# Pyro_Cut-Down.net
KiCad netlist of a schematic drawn in EAGLE
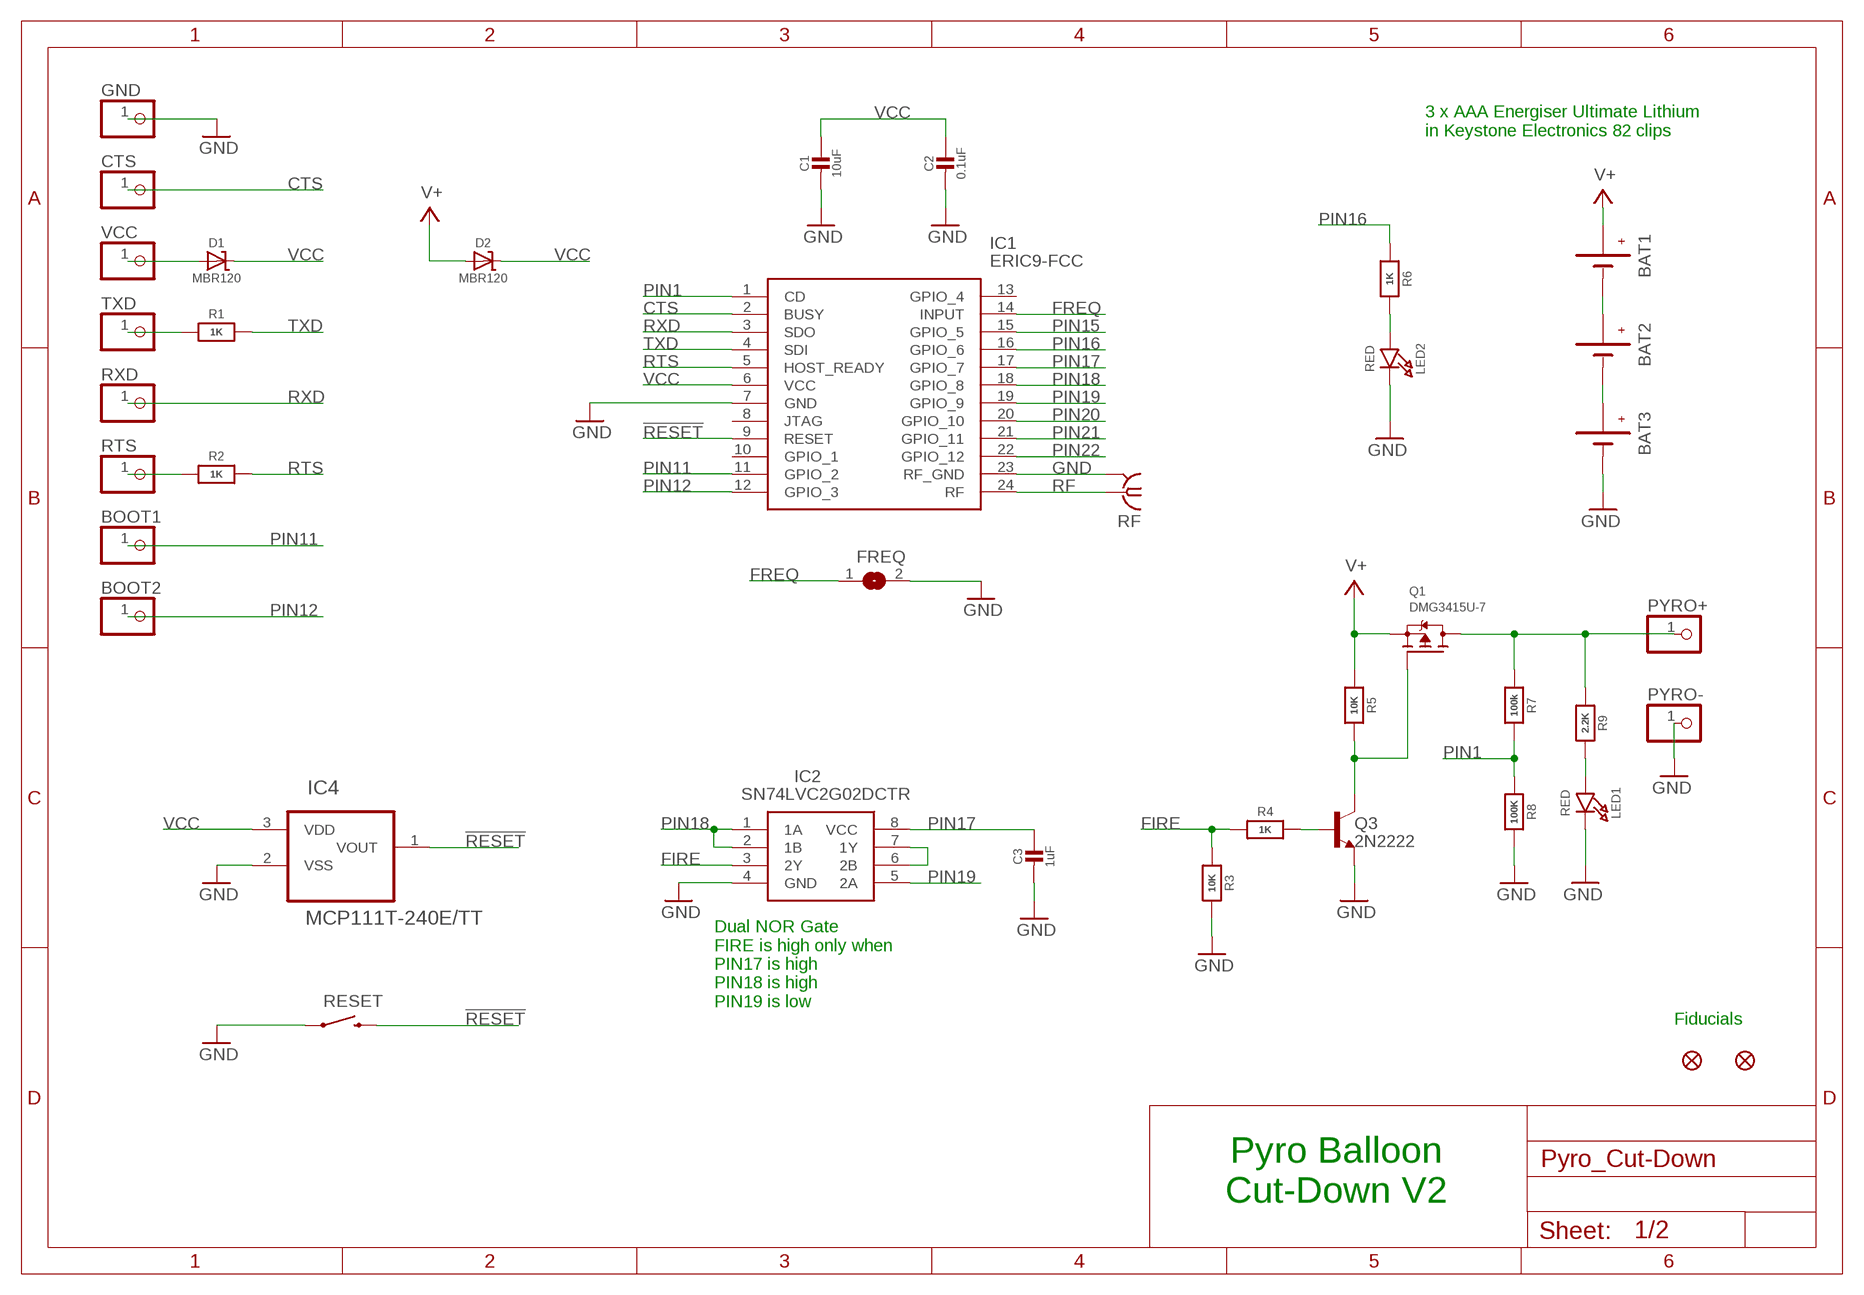
[diagram p0: schematic, sheet 1]
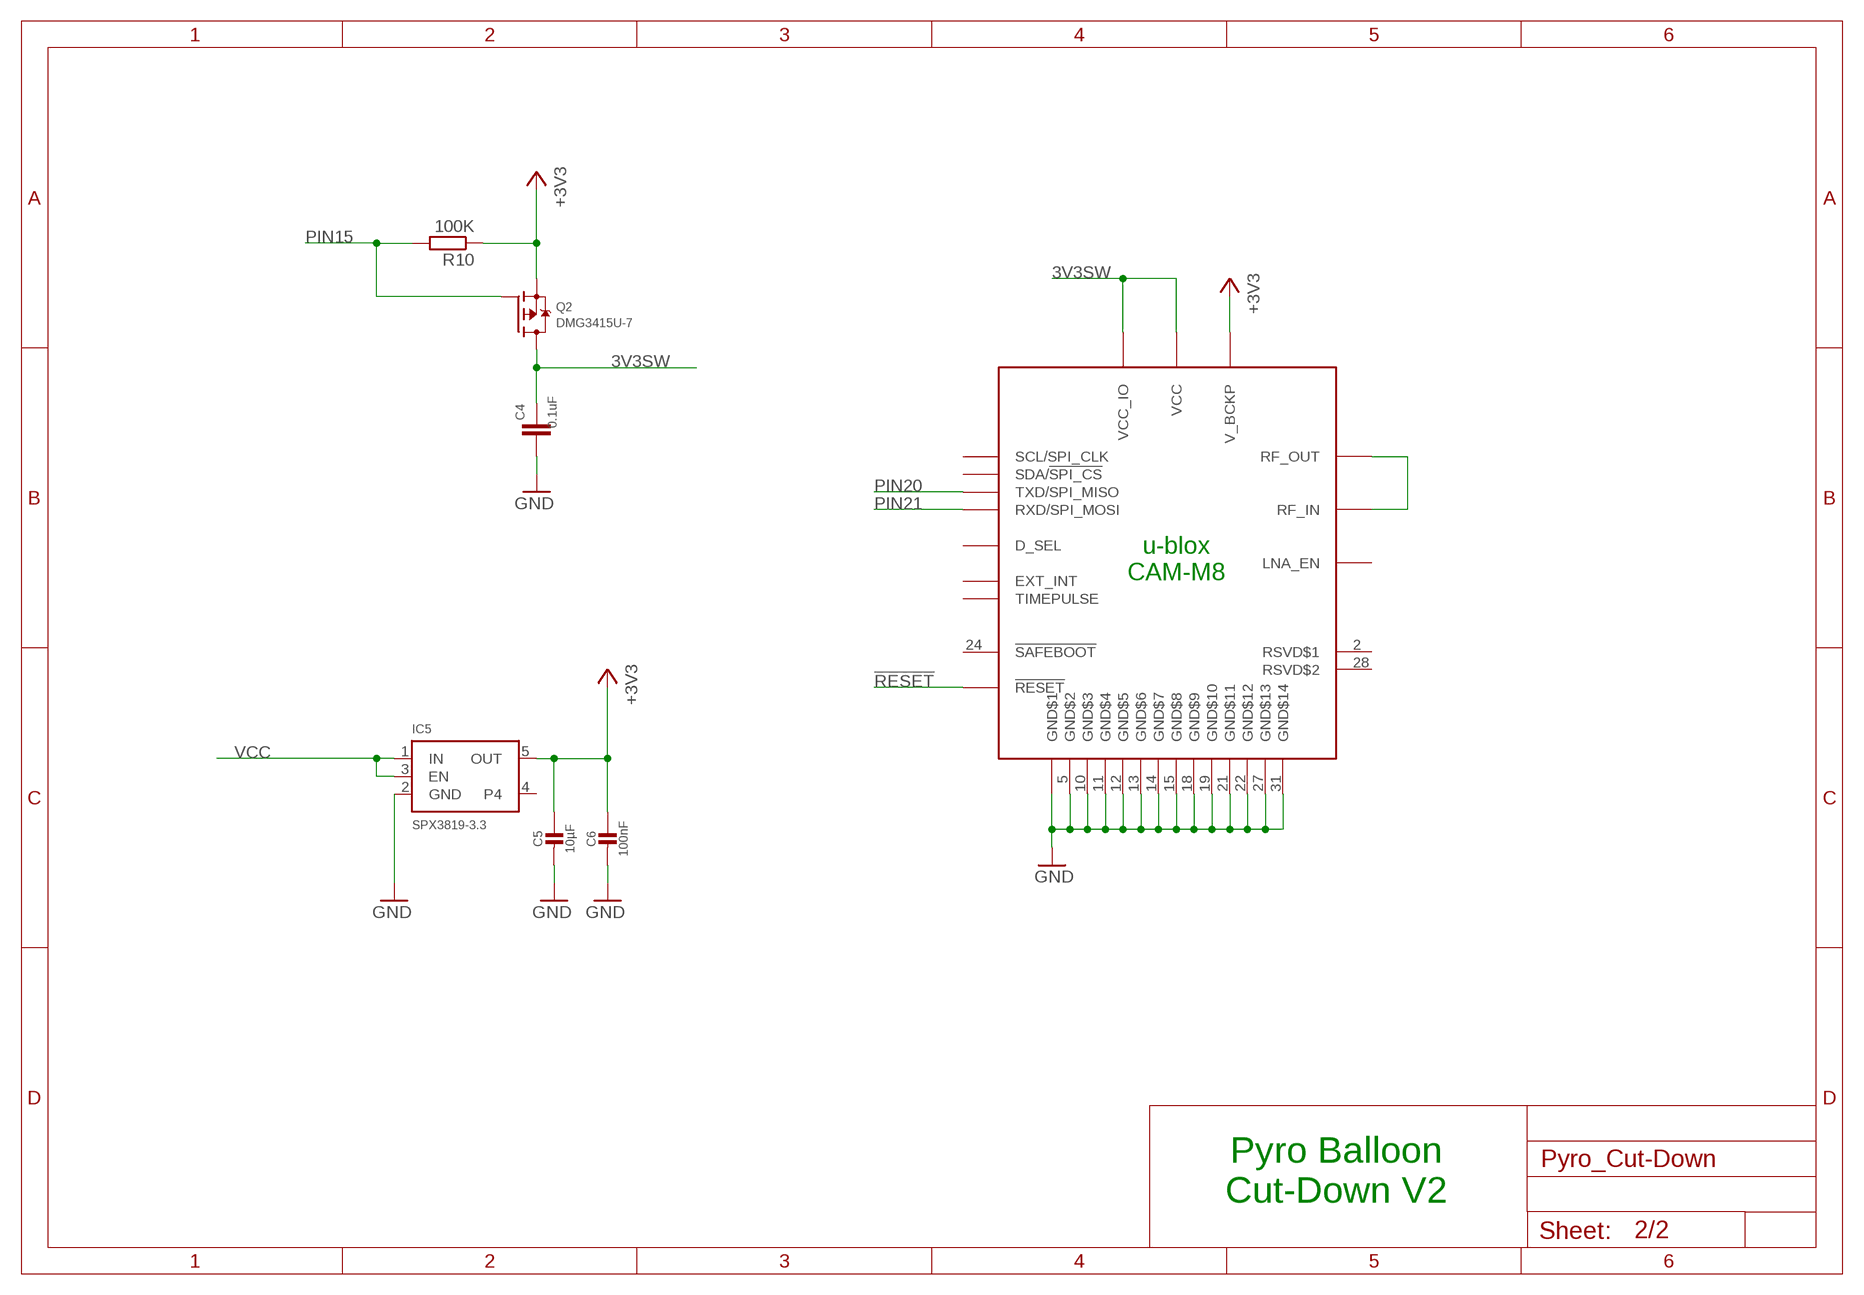
[diagram p1: schematic, sheet 2]

(export (version "E")
  (design (tool "Eeschema 10.0.6"))
  (components
    (comp (ref "C4")
      (value "0.1uF")
      (footprint "eagle-import:C0603")
      (libsource (lib "eagle-import") (part "C-EUC0603"))
    )
    (comp (ref "C5")
      (value "10µF")
      (footprint "eagle-import:0805-NO")
      (libsource (lib "eagle-import") (part "CAP_CERAMIC0805-NOOUTLINE"))
    )
    (comp (ref "C6")
      (value "100nF")
      (footprint "eagle-import:0603-NO")
      (libsource (lib "eagle-import") (part "CAP_CERAMIC0603_NO"))
    )
    (comp (ref "IC3")
      (value "CAM-M8")
      (footprint "eagle-import:CAM-M8")
      (libsource (lib "eagle-import") (part "CAM-M8"))
    )
    (comp (ref "IC5")
      (value "SPX3819-3.3")
      (footprint "eagle-import:SOT23-5")
      (libsource (lib "eagle-import") (part "VREG_SOT23-5"))
    )
    (comp (ref "Q2")
      (value "DMG3415U-7")
      (footprint "eagle-import:SOT23-WIDE")
      (libsource (lib "eagle-import") (part "MOSFET-PWIDE"))
    )
    (comp (ref "R10")
      (value "100K")
      (footprint "eagle-import:R0603")
      (libsource (lib "eagle-import") (part "R-EU_R0603"))
    )
    (comp (ref "BAT1")
      (value "BATTERYKEYSTONE82")
      (footprint "eagle-import:BATTERY-AAA-KEYSTONE82")
      (libsource (lib "eagle-import") (part "BATTERYKEYSTONE82"))
    )
    (comp (ref "BAT2")
      (value "BATTERYKEYSTONE82")
      (footprint "eagle-import:BATTERY-AAA-KEYSTONE82")
      (libsource (lib "eagle-import") (part "BATTERYKEYSTONE82"))
    )
    (comp (ref "BAT3")
      (value "BATTERYKEYSTONE82")
      (footprint "eagle-import:BATTERY-AAA-KEYSTONE82")
      (libsource (lib "eagle-import") (part "BATTERYKEYSTONE82"))
    )
    (comp (ref "BOOT1")
      (value "PINHD-1X1")
      (footprint "eagle-import:1X01")
      (libsource (lib "eagle-import") (part "PINHD-1X1"))
    )
    (comp (ref "BOOT2")
      (value "PINHD-1X1")
      (footprint "eagle-import:1X01")
      (libsource (lib "eagle-import") (part "PINHD-1X1"))
    )
    (comp (ref "C1")
      (value "10uF")
      (footprint "eagle-import:0805-NO")
      (libsource (lib "eagle-import") (part "CAP_CERAMIC0805-NOOUTLINE"))
    )
    (comp (ref "C2")
      (value "0.1uF")
      (footprint "eagle-import:0603-NO")
      (libsource (lib "eagle-import") (part "CAP_CERAMIC0603_NO"))
    )
    (comp (ref "C3")
      (value "1uF")
      (footprint "eagle-import:0603-NO")
      (libsource (lib "eagle-import") (part "CAP_CERAMIC0603_NO"))
    )
    (comp (ref "CTS")
      (value "PINHD-1X1")
      (footprint "eagle-import:1X01")
      (libsource (lib "eagle-import") (part "PINHD-1X1"))
    )
    (comp (ref "D1")
      (value "MBR120")
      (footprint "eagle-import:SOD-123")
      (libsource (lib "eagle-import") (part "DIODE-SCHOTTKYSOD-123"))
    )
    (comp (ref "D2")
      (value "MBR120")
      (footprint "eagle-import:SOD-123")
      (libsource (lib "eagle-import") (part "DIODE-SCHOTTKYSOD-123"))
    )
    (comp (ref "FD1")
      (value "FIDUCIAL1X2")
      (footprint "eagle-import:FIDUCIAL-1X2")
      (libsource (lib "eagle-import") (part "FIDUCIAL1X2"))
    )
    (comp (ref "FD2")
      (value "FIDUCIAL1X2")
      (footprint "eagle-import:FIDUCIAL-1X2")
      (libsource (lib "eagle-import") (part "FIDUCIAL1X2"))
    )
    (comp (ref "FREQ")
      (value "SOLDERJUMPER")
      (footprint "eagle-import:SOLDERJUMPER_ARROW_NOPASTE")
      (libsource (lib "eagle-import") (part "SOLDERJUMPER"))
    )
    (comp (ref "GND")
      (value "PINHD-1X1")
      (footprint "eagle-import:1X01")
      (libsource (lib "eagle-import") (part "PINHD-1X1"))
    )
    (comp (ref "IC1")
      (value "ERIC9-FCC")
      (footprint "eagle-import:ERIC4")
      (fields (field (name "ARROW_PART_NUMBER") "eRIC9-FCC"))
      (libsource (lib "eagle-import") (part "ERIC9-FCC"))
    )
    (comp (ref "IC2")
      (value "SN74LVC2G02DCTR")
      (footprint "eagle-import:SOP65P400X130-8N")
      (libsource (lib "eagle-import") (part "SN74LVC2G02DCTR"))
    )
    (comp (ref "IC4")
      (value "MCP111T-240E/TT")
      (footprint "eagle-import:SOT95P237X112-3N")
      (fields (field (name "MPN") "MCP111T-270E/TT") (field (name "MPN_1") "MCP111T-240E/TT"))
      (libsource (lib "eagle-import") (part "MCP111T-270E/TT"))
    )
    (comp (ref "LED1")
      (value "RED")
      (footprint "eagle-import:CHIPLED_0805_NOOUTLINE")
      (libsource (lib "eagle-import") (part "LED0805_NOOUTLINE"))
    )
    (comp (ref "LED2")
      (value "RED")
      (footprint "eagle-import:CHIPLED_0805_NOOUTLINE")
      (libsource (lib "eagle-import") (part "LED0805_NOOUTLINE"))
    )
    (comp (ref "PYRO+")
      (value "PINHD-1X1")
      (footprint "eagle-import:1X01")
      (libsource (lib "eagle-import") (part "PINHD-1X1"))
    )
    (comp (ref "PYRO-")
      (value "PINHD-1X1")
      (footprint "eagle-import:1X01")
      (libsource (lib "eagle-import") (part "PINHD-1X1"))
    )
    (comp (ref "Q1")
      (value "DMG3415U-7")
      (footprint "eagle-import:SOT23-WIDE")
      (libsource (lib "eagle-import") (part "MOSFET-PWIDE"))
    )
    (comp (ref "Q3")
      (value "2N2222")
      (footprint "eagle-import:SOT23-BEC")
      (libsource (lib "eagle-import") (part "-NPN-SOT23-BECMMBT2222ALT1"))
    )
    (comp (ref "R1")
      (value "1K")
      (footprint "eagle-import:0603-NO")
      (libsource (lib "eagle-import") (part "RESISTOR_0603_NOOUT"))
    )
    (comp (ref "R2")
      (value "1K")
      (footprint "eagle-import:0603-NO")
      (libsource (lib "eagle-import") (part "RESISTOR_0603_NOOUT"))
    )
    (comp (ref "R3")
      (value "10K")
      (footprint "eagle-import:0603-NO")
      (libsource (lib "eagle-import") (part "RESISTOR_0603_NOOUT"))
    )
    (comp (ref "R4")
      (value "1K")
      (footprint "eagle-import:0603-NO")
      (libsource (lib "eagle-import") (part "RESISTOR_0603_NOOUT"))
    )
    (comp (ref "R5")
      (value "10K")
      (footprint "eagle-import:0603-NO")
      (libsource (lib "eagle-import") (part "RESISTOR_0603_NOOUT"))
    )
    (comp (ref "R6")
      (value "1K")
      (footprint "eagle-import:0603-NO")
      (libsource (lib "eagle-import") (part "RESISTOR_0603_NOOUT"))
    )
    (comp (ref "R7")
      (value "100k")
      (footprint "eagle-import:0603-NO")
      (libsource (lib "eagle-import") (part "RESISTOR_0603_NOOUT"))
    )
    (comp (ref "R8")
      (value "100K")
      (footprint "eagle-import:0603-NO")
      (libsource (lib "eagle-import") (part "RESISTOR_0603_NOOUT"))
    )
    (comp (ref "R9")
      (value "2.2K")
      (footprint "eagle-import:0603-NO")
      (libsource (lib "eagle-import") (part "RESISTOR_0603_NOOUT"))
    )
    (comp (ref "RESET")
      (value "SWITCH-MOMENTARY-2PTH")
      (footprint "eagle-import:TACTILE-PTH")
      (libsource (lib "eagle-import") (part "SWITCH-MOMENTARY-2PTH"))
    )
    (comp (ref "RF")
      (value "SMA-142-0711-821/826")
      (footprint "eagle-import:J502-ND-142-0711-821_826")
      (fields (field (name "MF") "JOHNSON COMPONENTS") (field (name "MPN") "142-0711-821"))
      (libsource (lib "eagle-import") (part "SMA-142-0711-821/826"))
    )
    (comp (ref "RTS")
      (value "PINHD-1X1")
      (footprint "eagle-import:1X01")
      (libsource (lib "eagle-import") (part "PINHD-1X1"))
    )
    (comp (ref "RXD")
      (value "PINHD-1X1")
      (footprint "eagle-import:1X01")
      (libsource (lib "eagle-import") (part "PINHD-1X1"))
    )
    (comp (ref "TXD")
      (value "PINHD-1X1")
      (footprint "eagle-import:1X01")
      (libsource (lib "eagle-import") (part "PINHD-1X1"))
    )
    (comp (ref "VCC")
      (value "PINHD-1X1")
      (footprint "eagle-import:1X01")
      (libsource (lib "eagle-import") (part "PINHD-1X1"))
    )
  )
  (nets
    (net (code "1") (name "+3V3") (class "Default")
      (node (ref "C5") (pin "1") (pinfunction "1_1") (pintype "passive"))
      (node (ref "C6") (pin "1") (pinfunction "1_1") (pintype "passive"))
      (node (ref "IC3") (pin "8") (pinfunction "V_BCKP_8") (pintype "power_in"))
      (node (ref "IC5") (pin "5") (pinfunction "OUT_5") (pintype "power_in"))
      (node (ref "Q2") (pin "2") (pinfunction "S_2") (pintype "passive"))
      (node (ref "R10") (pin "1") (pinfunction "1_1") (pintype "passive"))
    )
    (net (code "2") (name "3V3SW") (class "Default")
      (node (ref "C4") (pin "1") (pinfunction "1_1") (pintype "passive"))
      (node (ref "IC3") (pin "1") (pinfunction "VCC_IO_1") (pintype "power_in"))
      (node (ref "IC3") (pin "9") (pinfunction "VCC_9") (pintype "power_in"))
      (node (ref "Q2") (pin "3") (pinfunction "D_3") (pintype "passive"))
    )
    (net (code "3") (name "CTS") (class "Default")
      (node (ref "CTS") (pin "1") (pinfunction "1_1") (pintype "passive"))
      (node (ref "IC1") (pin "2") (pinfunction "BUSY_2") (pintype "bidirectional"))
    )
    (net (code "4") (name "FIRE") (class "Default")
      (node (ref "IC2") (pin "3") (pinfunction "2Y_3") (pintype "bidirectional"))
      (node (ref "R3") (pin "1") (pinfunction "1_1") (pintype "passive"))
      (node (ref "R4") (pin "1") (pinfunction "1_1") (pintype "passive"))
    )
    (net (code "5") (name "FREQ") (class "Default")
      (node (ref "FREQ") (pin "1") (pinfunction "1_1") (pintype "passive"))
      (node (ref "IC1") (pin "14") (pinfunction "INPUT_14") (pintype "bidirectional"))
    )
    (net (code "6") (name "GND") (class "Default")
      (node (ref "BAT3") (pin "GND@1") (pinfunction "-_GND@1") (pintype "power_in"))
      (node (ref "BAT3") (pin "GND@2") (pinfunction "-_GND@2") (pintype "power_in"))
      (node (ref "C1") (pin "2") (pinfunction "2_2") (pintype "passive"))
      (node (ref "C2") (pin "2") (pinfunction "2_2") (pintype "passive"))
      (node (ref "C3") (pin "2") (pinfunction "2_2") (pintype "passive"))
      (node (ref "C4") (pin "2") (pinfunction "2_2") (pintype "passive"))
      (node (ref "C5") (pin "2") (pinfunction "2_2") (pintype "passive"))
      (node (ref "C6") (pin "2") (pinfunction "2_2") (pintype "passive"))
      (node (ref "FREQ") (pin "2") (pinfunction "2_2") (pintype "passive"))
      (node (ref "GND") (pin "1") (pinfunction "1_1") (pintype "passive"))
      (node (ref "IC1") (pin "23") (pinfunction "RF_GND_23") (pintype "bidirectional"))
      (node (ref "IC1") (pin "7") (pinfunction "GND_7") (pintype "bidirectional"))
      (node (ref "IC2") (pin "4") (pinfunction "GND_4") (pintype "bidirectional"))
      (node (ref "IC3") (pin "10") (pinfunction "GND$3_10") (pintype "power_in"))
      (node (ref "IC3") (pin "11") (pinfunction "GND$4_11") (pintype "power_in"))
      (node (ref "IC3") (pin "12") (pinfunction "GND$5_12") (pintype "power_in"))
      (node (ref "IC3") (pin "13") (pinfunction "GND$6_13") (pintype "power_in"))
      (node (ref "IC3") (pin "14") (pinfunction "GND$7_14") (pintype "power_in"))
      (node (ref "IC3") (pin "15") (pinfunction "GND$8_15") (pintype "power_in"))
      (node (ref "IC3") (pin "18") (pinfunction "GND$9_18") (pintype "power_in"))
      (node (ref "IC3") (pin "19") (pinfunction "GND$10_19") (pintype "power_in"))
      (node (ref "IC3") (pin "21") (pinfunction "GND$11_21") (pintype "power_in"))
      (node (ref "IC3") (pin "22") (pinfunction "GND$12_22") (pintype "power_in"))
      (node (ref "IC3") (pin "27") (pinfunction "GND$13_27") (pintype "power_in"))
      (node (ref "IC3") (pin "31") (pinfunction "GND$14_31") (pintype "power_in"))
      (node (ref "IC3") (pin "4") (pinfunction "GND$1_4") (pintype "power_in"))
      (node (ref "IC3") (pin "5") (pinfunction "GND$2_5") (pintype "power_in"))
      (node (ref "IC4") (pin "2") (pinfunction "VSS_2") (pintype "power_in"))
      (node (ref "IC5") (pin "2") (pinfunction "GND_2") (pintype "power_in"))
      (node (ref "LED1") (pin "C") (pinfunction "C_C") (pintype "passive"))
      (node (ref "LED2") (pin "C") (pinfunction "C_C") (pintype "passive"))
      (node (ref "PYRO-") (pin "1") (pinfunction "1_1") (pintype "passive"))
      (node (ref "Q3") (pin "E") (pinfunction "E_E") (pintype "passive"))
      (node (ref "R3") (pin "2") (pinfunction "2_2") (pintype "passive"))
      (node (ref "R8") (pin "2") (pinfunction "2_2") (pintype "passive"))
      (node (ref "RESET") (pin "1") (pinfunction "1_1") (pintype "passive"))
      (node (ref "RF") (pin "G@1") (pinfunction "2_G@1") (pintype "passive"))
      (node (ref "RF") (pin "G@2") (pinfunction "2_G@2") (pintype "passive"))
      (node (ref "RF") (pin "G@3") (pinfunction "2_G@3") (pintype "passive"))
      (node (ref "RF") (pin "G@4") (pinfunction "2_G@4") (pintype "passive"))
    )
    (net (code "7") (name "Net-(BAT1---PadGND@1)") (class "Default")
      (node (ref "BAT1") (pin "GND@1") (pinfunction "-_GND@1") (pintype "power_in"))
      (node (ref "BAT1") (pin "GND@2") (pinfunction "-_GND@2") (pintype "power_in"))
      (node (ref "BAT2") (pin "PWR@1") (pinfunction "+_PWR@1") (pintype "power_in"))
      (node (ref "BAT2") (pin "PWR@2") (pinfunction "+_PWR@2") (pintype "power_in"))
    )
    (net (code "8") (name "Net-(BAT2---PadGND@1)") (class "Default")
      (node (ref "BAT2") (pin "GND@1") (pinfunction "-_GND@1") (pintype "power_in"))
      (node (ref "BAT2") (pin "GND@2") (pinfunction "-_GND@2") (pintype "power_in"))
      (node (ref "BAT3") (pin "PWR@1") (pinfunction "+_PWR@1") (pintype "power_in"))
      (node (ref "BAT3") (pin "PWR@2") (pinfunction "+_PWR@2") (pintype "power_in"))
    )
    (net (code "9") (name "Net-(D1-PadA)") (class "Default")
      (node (ref "D1") (pin "A") (pinfunction "A_A") (pintype "passive"))
      (node (ref "VCC") (pin "1") (pinfunction "1_1") (pintype "passive"))
    )
    (net (code "10") (name "Net-(IC2-1Y)") (class "Default")
      (node (ref "IC2") (pin "6") (pinfunction "2B_6") (pintype "bidirectional"))
      (node (ref "IC2") (pin "7") (pinfunction "1Y_7") (pintype "bidirectional"))
    )
    (net (code "11") (name "Net-(IC3-RF_IN)") (class "Default")
      (node (ref "IC3") (pin "16") (pinfunction "RF_OUT_16") (pintype "output"))
      (node (ref "IC3") (pin "17") (pinfunction "RF_IN_17") (pintype "input"))
    )
    (net (code "12") (name "Net-(LED1-PadA)") (class "Default")
      (node (ref "LED1") (pin "A") (pinfunction "A_A") (pintype "passive"))
      (node (ref "R9") (pin "2") (pinfunction "2_2") (pintype "passive"))
    )
    (net (code "13") (name "Net-(LED2-PadA)") (class "Default")
      (node (ref "LED2") (pin "A") (pinfunction "A_A") (pintype "passive"))
      (node (ref "R6") (pin "2") (pinfunction "2_2") (pintype "passive"))
    )
    (net (code "14") (name "Net-(Q1-D)") (class "Default")
      (node (ref "PYRO+") (pin "1") (pinfunction "1_1") (pintype "passive"))
      (node (ref "Q1") (pin "3") (pinfunction "D_3") (pintype "passive"))
      (node (ref "R7") (pin "1") (pinfunction "1_1") (pintype "passive"))
      (node (ref "R9") (pin "1") (pinfunction "1_1") (pintype "passive"))
    )
    (net (code "15") (name "Net-(Q1-G)") (class "Default")
      (node (ref "Q1") (pin "1") (pinfunction "G_1") (pintype "passive"))
      (node (ref "Q3") (pin "C") (pinfunction "C_C") (pintype "passive"))
      (node (ref "R5") (pin "2") (pinfunction "2_2") (pintype "passive"))
    )
    (net (code "16") (name "Net-(Q3-PadB)") (class "Default")
      (node (ref "Q3") (pin "B") (pinfunction "B_B") (pintype "passive"))
      (node (ref "R4") (pin "2") (pinfunction "2_2") (pintype "passive"))
    )
    (net (code "17") (name "Net-(R1-Pad1)") (class "Default")
      (node (ref "R1") (pin "1") (pinfunction "1_1") (pintype "passive"))
      (node (ref "TXD") (pin "1") (pinfunction "1_1") (pintype "passive"))
    )
    (net (code "18") (name "Net-(R2-Pad1)") (class "Default")
      (node (ref "R2") (pin "1") (pinfunction "1_1") (pintype "passive"))
      (node (ref "RTS") (pin "1") (pinfunction "1_1") (pintype "passive"))
    )
    (net (code "19") (name "PIN1") (class "Default")
      (node (ref "IC1") (pin "1") (pinfunction "CD_1") (pintype "bidirectional"))
      (node (ref "R7") (pin "2") (pinfunction "2_2") (pintype "passive"))
      (node (ref "R8") (pin "1") (pinfunction "1_1") (pintype "passive"))
    )
    (net (code "20") (name "PIN11") (class "Default")
      (node (ref "BOOT1") (pin "1") (pinfunction "1_1") (pintype "passive"))
      (node (ref "IC1") (pin "11") (pinfunction "GPIO_2_11") (pintype "bidirectional"))
    )
    (net (code "21") (name "PIN12") (class "Default")
      (node (ref "BOOT2") (pin "1") (pinfunction "1_1") (pintype "passive"))
      (node (ref "IC1") (pin "12") (pinfunction "GPIO_3_12") (pintype "bidirectional"))
    )
    (net (code "22") (name "PIN15") (class "Default")
      (node (ref "IC1") (pin "15") (pinfunction "GPIO_5_15") (pintype "bidirectional"))
      (node (ref "Q2") (pin "1") (pinfunction "G_1") (pintype "passive"))
      (node (ref "R10") (pin "2") (pinfunction "2_2") (pintype "passive"))
    )
    (net (code "23") (name "PIN16") (class "Default")
      (node (ref "IC1") (pin "16") (pinfunction "GPIO_6_16") (pintype "bidirectional"))
      (node (ref "R6") (pin "1") (pinfunction "1_1") (pintype "passive"))
    )
    (net (code "24") (name "PIN17") (class "Default")
      (node (ref "C3") (pin "1") (pinfunction "1_1") (pintype "passive"))
      (node (ref "IC1") (pin "17") (pinfunction "GPIO_7_17") (pintype "bidirectional"))
      (node (ref "IC2") (pin "8") (pinfunction "VCC_8") (pintype "bidirectional"))
    )
    (net (code "25") (name "PIN18") (class "Default")
      (node (ref "IC1") (pin "18") (pinfunction "GPIO_8_18") (pintype "bidirectional"))
      (node (ref "IC2") (pin "1") (pinfunction "1A_1") (pintype "bidirectional"))
      (node (ref "IC2") (pin "2") (pinfunction "1B_2") (pintype "bidirectional"))
    )
    (net (code "26") (name "PIN19") (class "Default")
      (node (ref "IC1") (pin "19") (pinfunction "GPIO_9_19") (pintype "bidirectional"))
      (node (ref "IC2") (pin "5") (pinfunction "2A_5") (pintype "bidirectional"))
    )
    (net (code "27") (name "PIN20") (class "Default")
      (node (ref "IC1") (pin "20") (pinfunction "GPIO_10_20") (pintype "bidirectional"))
      (node (ref "IC3") (pin "25") (pinfunction "TXD/SPI_MISO_25") (pintype "output"))
    )
    (net (code "28") (name "PIN21") (class "Default")
      (node (ref "IC1") (pin "21") (pinfunction "GPIO_11_21") (pintype "bidirectional"))
      (node (ref "IC3") (pin "26") (pinfunction "RXD/SPI_MOSI_26") (pintype "input"))
    )
    (net (code "29") (name "PIN22") (class "Default")
      (node (ref "IC1") (pin "22") (pinfunction "GPIO_12_22") (pintype "bidirectional"))
    )
    (net (code "30") (name "RF") (class "Default")
      (node (ref "IC1") (pin "24") (pinfunction "RF_24") (pintype "bidirectional"))
      (node (ref "RF") (pin "1") (pinfunction "1_1") (pintype "passive"))
    )
    (net (code "31") (name "RTS") (class "Default")
      (node (ref "IC1") (pin "5") (pinfunction "HOST_READY_5") (pintype "bidirectional"))
      (node (ref "R2") (pin "2") (pinfunction "2_2") (pintype "passive"))
    )
    (net (code "32") (name "RXD") (class "Default")
      (node (ref "IC1") (pin "3") (pinfunction "SDO_3") (pintype "bidirectional"))
      (node (ref "RXD") (pin "1") (pinfunction "1_1") (pintype "passive"))
    )
    (net (code "33") (name "TXD") (class "Default")
      (node (ref "IC1") (pin "4") (pinfunction "SDI_4") (pintype "bidirectional"))
      (node (ref "R1") (pin "2") (pinfunction "2_2") (pintype "passive"))
    )
    (net (code "34") (name "V+") (class "Default")
      (node (ref "BAT1") (pin "PWR@1") (pinfunction "+_PWR@1") (pintype "power_in"))
      (node (ref "BAT1") (pin "PWR@2") (pinfunction "+_PWR@2") (pintype "power_in"))
      (node (ref "D2") (pin "A") (pinfunction "A_A") (pintype "passive"))
      (node (ref "Q1") (pin "2") (pinfunction "S_2") (pintype "passive"))
      (node (ref "R5") (pin "1") (pinfunction "1_1") (pintype "passive"))
    )
    (net (code "35") (name "VCC") (class "Default")
      (node (ref "C1") (pin "1") (pinfunction "1_1") (pintype "passive"))
      (node (ref "C2") (pin "1") (pinfunction "1_1") (pintype "passive"))
      (node (ref "D1") (pin "C") (pinfunction "C_C") (pintype "passive"))
      (node (ref "D2") (pin "C") (pinfunction "C_C") (pintype "passive"))
      (node (ref "IC1") (pin "6") (pinfunction "VCC_6") (pintype "bidirectional"))
      (node (ref "IC4") (pin "3") (pinfunction "VDD_3") (pintype "power_in"))
      (node (ref "IC5") (pin "1") (pinfunction "IN_1") (pintype "power_in"))
      (node (ref "IC5") (pin "3") (pinfunction "EN_3") (pintype "input"))
    )
    (net (code "36") (name "unconnected-(IC1-GPIO_1-Pad10)") (class "Default")
      (node (ref "IC1") (pin "10") (pinfunction "GPIO_1_10") (pintype "bidirectional"))
    )
    (net (code "37") (name "unconnected-(IC1-GPIO_4-Pad13)") (class "Default")
      (node (ref "IC1") (pin "13") (pinfunction "GPIO_4_13") (pintype "bidirectional"))
    )
    (net (code "38") (name "unconnected-(IC1-JTAG-Pad8)") (class "Default")
      (node (ref "IC1") (pin "8") (pinfunction "JTAG_8") (pintype "bidirectional"))
    )
    (net (code "39") (name "unconnected-(IC3-D_SEL-Pad20)") (class "Default")
      (node (ref "IC3") (pin "20") (pinfunction "D_SEL_20") (pintype "input"))
    )
    (net (code "40") (name "unconnected-(IC3-EXT_INT-Pad7)") (class "Default")
      (node (ref "IC3") (pin "7") (pinfunction "EXT_INT_7") (pintype "bidirectional"))
    )
    (net (code "41") (name "unconnected-(IC3-LNA_EN-Pad30)") (class "Default")
      (node (ref "IC3") (pin "30") (pinfunction "LNA_EN_30") (pintype "output"))
    )
    (net (code "42") (name "unconnected-(IC3-RSVD$1-Pad2)") (class "Default")
      (node (ref "IC3") (pin "2") (pinfunction "RSVD$1_2") (pintype "no_connect"))
    )
    (net (code "43") (name "unconnected-(IC3-RSVD$2-Pad28)") (class "Default")
      (node (ref "IC3") (pin "28") (pinfunction "RSVD$2_28") (pintype "no_connect"))
    )
    (net (code "44") (name "unconnected-(IC3-SCL{slash}SPI_CLK-Pad6)") (class "Default")
      (node (ref "IC3") (pin "6") (pinfunction "SCL/SPI_CLK_6") (pintype "input"))
    )
    (net (code "45") (name "unconnected-(IC3-SDA{slash}~{SPI_CS}-Pad3)") (class "Default")
      (node (ref "IC3") (pin "3") (pinfunction "SDA/~{SPI_CS}_3") (pintype "bidirectional"))
    )
    (net (code "46") (name "unconnected-(IC3-TIMEPULSE-Pad29)") (class "Default")
      (node (ref "IC3") (pin "29") (pinfunction "TIMEPULSE_29") (pintype "output"))
    )
    (net (code "47") (name "unconnected-(IC3-~{SAFEBOOT}-Pad24)") (class "Default")
      (node (ref "IC3") (pin "24") (pinfunction "~{SAFEBOOT}_24") (pintype "input"))
    )
    (net (code "48") (name "unconnected-(IC5-P4-Pad4)") (class "Default")
      (node (ref "IC5") (pin "4") (pinfunction "P4_4") (pintype "bidirectional"))
    )
    (net (code "49") (name "~{RESET}") (class "Default")
      (node (ref "IC1") (pin "9") (pinfunction "RESET_9") (pintype "bidirectional"))
      (node (ref "IC3") (pin "23") (pinfunction "~{RESET}_23") (pintype "input"))
      (node (ref "IC4") (pin "1") (pinfunction "VOUT_1") (pintype "output"))
      (node (ref "RESET") (pin "3") (pinfunction "2_3") (pintype "passive"))
    )
  )
)
